# switch.net
KiCad netlist of a schematic drawn in Altium Designer
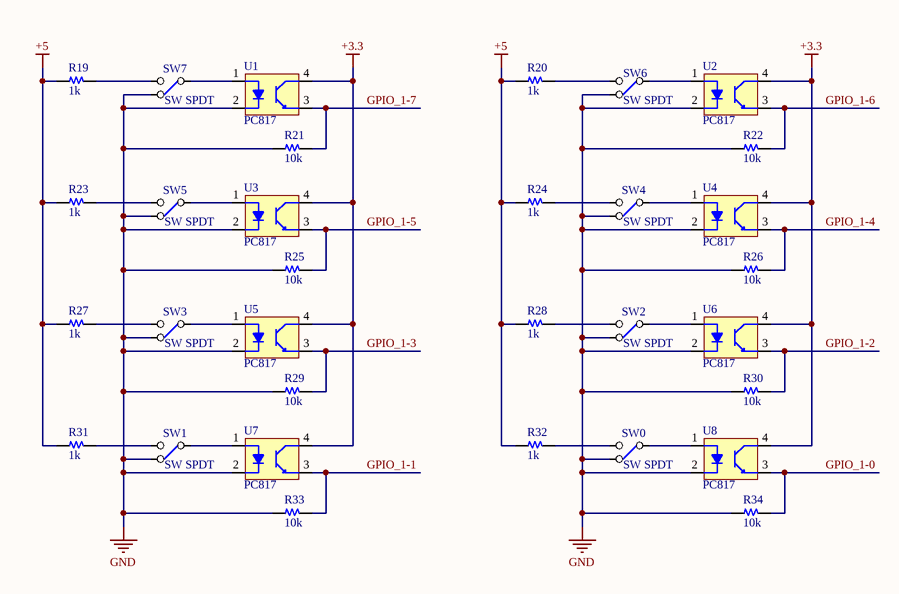
[diagram p0: switch.SchDoc]

(export (version "E")
  (design (tool "Eeschema 10.0.6"))
  (components
    (comp (ref "R19")
      (value "1k")
      (footprint "R 0603")
      (description "Resistor")
      (libsource (lib "chipfc_libs") (part "Resistor"))
    )
    (comp (ref "R20")
      (value "1k")
      (footprint "R 0603")
      (description "Resistor")
      (libsource (lib "chipfc_libs") (part "Resistor"))
    )
    (comp (ref "R21")
      (value "10k")
      (footprint "R 0603")
      (description "Resistor")
      (libsource (lib "chipfc_libs") (part "Resistor"))
    )
    (comp (ref "R22")
      (value "10k")
      (footprint "R 0603")
      (description "Resistor")
      (libsource (lib "chipfc_libs") (part "Resistor"))
    )
    (comp (ref "R23")
      (value "1k")
      (footprint "R 0603")
      (description "Resistor")
      (libsource (lib "chipfc_libs") (part "Resistor"))
    )
    (comp (ref "R24")
      (value "1k")
      (footprint "R 0603")
      (description "Resistor")
      (libsource (lib "chipfc_libs") (part "Resistor"))
    )
    (comp (ref "R25")
      (value "10k")
      (footprint "R 0603")
      (description "Resistor")
      (libsource (lib "chipfc_libs") (part "Resistor"))
    )
    (comp (ref "R26")
      (value "10k")
      (footprint "R 0603")
      (description "Resistor")
      (libsource (lib "chipfc_libs") (part "Resistor"))
    )
    (comp (ref "R27")
      (value "1k")
      (footprint "R 0603")
      (description "Resistor")
      (libsource (lib "chipfc_libs") (part "Resistor"))
    )
    (comp (ref "R28")
      (value "1k")
      (footprint "R 0603")
      (description "Resistor")
      (libsource (lib "chipfc_libs") (part "Resistor"))
    )
    (comp (ref "R29")
      (value "10k")
      (footprint "R 0603")
      (description "Resistor")
      (libsource (lib "chipfc_libs") (part "Resistor"))
    )
    (comp (ref "R30")
      (value "10k")
      (footprint "R 0603")
      (description "Resistor")
      (libsource (lib "chipfc_libs") (part "Resistor"))
    )
    (comp (ref "R31")
      (value "1k")
      (footprint "R 0603")
      (description "Resistor")
      (libsource (lib "chipfc_libs") (part "Resistor"))
    )
    (comp (ref "R32")
      (value "1k")
      (footprint "R 0603")
      (description "Resistor")
      (libsource (lib "chipfc_libs") (part "Resistor"))
    )
    (comp (ref "R33")
      (value "10k")
      (footprint "R 0603")
      (description "Resistor")
      (libsource (lib "chipfc_libs") (part "Resistor"))
    )
    (comp (ref "R34")
      (value "10k")
      (footprint "R 0603")
      (description "Resistor")
      (libsource (lib "chipfc_libs") (part "Resistor"))
    )
    (comp (ref "SW0")
      (value "SW SPDT")
      (footprint "SW/3/SPDT/SS12D10")
      (libsource (lib "chipfc_libs") (part "SW SPDT"))
    )
    (comp (ref "SW1")
      (value "SW SPDT")
      (footprint "SW/3/SPDT/SS12D10")
      (libsource (lib "chipfc_libs") (part "SW SPDT"))
    )
    (comp (ref "SW2")
      (value "SW SPDT")
      (footprint "SW/3/SPDT/SS12D10")
      (libsource (lib "chipfc_libs") (part "SW SPDT"))
    )
    (comp (ref "SW3")
      (value "SW SPDT")
      (footprint "SW/3/SPDT/SS12D10")
      (libsource (lib "chipfc_libs") (part "SW SPDT"))
    )
    (comp (ref "SW4")
      (value "SW SPDT")
      (footprint "SW/3/SPDT/SS12D10")
      (libsource (lib "chipfc_libs") (part "SW SPDT"))
    )
    (comp (ref "SW5")
      (value "SW SPDT")
      (footprint "SW/3/SPDT/SS12D10")
      (libsource (lib "chipfc_libs") (part "SW SPDT"))
    )
    (comp (ref "SW6")
      (value "SW SPDT")
      (footprint "SW/3/SPDT/SS12D10")
      (libsource (lib "chipfc_libs") (part "SW SPDT"))
    )
    (comp (ref "SW7")
      (value "SW SPDT")
      (footprint "SW/3/SPDT/SS12D10")
      (libsource (lib "chipfc_libs") (part "SW SPDT"))
    )
    (comp (ref "U1")
      (value "PC817")
      (footprint "SOP4 - PC817")
      (description "Opto PC817B")
      (libsource (lib "bs_libs") (part "PC817"))
    )
    (comp (ref "U2")
      (value "PC817")
      (footprint "SOP4 - PC817")
      (description "Opto PC817B")
      (libsource (lib "bs_libs") (part "PC817"))
    )
    (comp (ref "U3")
      (value "PC817")
      (footprint "SOP4 - PC817")
      (description "Opto PC817B")
      (libsource (lib "bs_libs") (part "PC817"))
    )
    (comp (ref "U4")
      (value "PC817")
      (footprint "SOP4 - PC817")
      (description "Opto PC817B")
      (libsource (lib "bs_libs") (part "PC817"))
    )
    (comp (ref "U5")
      (value "PC817")
      (footprint "SOP4 - PC817")
      (description "Opto PC817B")
      (libsource (lib "bs_libs") (part "PC817"))
    )
    (comp (ref "U6")
      (value "PC817")
      (footprint "SOP4 - PC817")
      (description "Opto PC817B")
      (libsource (lib "bs_libs") (part "PC817"))
    )
    (comp (ref "U7")
      (value "PC817")
      (footprint "SOP4 - PC817")
      (description "Opto PC817B")
      (libsource (lib "bs_libs") (part "PC817"))
    )
    (comp (ref "U8")
      (value "PC817")
      (footprint "SOP4 - PC817")
      (description "Opto PC817B")
      (libsource (lib "bs_libs") (part "PC817"))
    )
  )
  (nets
    (net (code "1") (name "+3.3") (class "Default")
      (node (ref "U1") (pin "4") (pinfunction "C_4") (pintype "passive"))
      (node (ref "U2") (pin "4") (pinfunction "C_4") (pintype "passive"))
      (node (ref "U3") (pin "4") (pinfunction "C_4") (pintype "passive"))
      (node (ref "U4") (pin "4") (pinfunction "C_4") (pintype "passive"))
      (node (ref "U5") (pin "4") (pinfunction "C_4") (pintype "passive"))
      (node (ref "U6") (pin "4") (pinfunction "C_4") (pintype "passive"))
      (node (ref "U7") (pin "4") (pinfunction "C_4") (pintype "passive"))
      (node (ref "U8") (pin "4") (pinfunction "C_4") (pintype "passive"))
    )
    (net (code "2") (name "+5") (class "Default")
      (node (ref "R19") (pin "1") (pinfunction "1_1") (pintype "passive"))
      (node (ref "R20") (pin "1") (pinfunction "1_1") (pintype "passive"))
      (node (ref "R23") (pin "1") (pinfunction "1_1") (pintype "passive"))
      (node (ref "R24") (pin "1") (pinfunction "1_1") (pintype "passive"))
      (node (ref "R27") (pin "1") (pinfunction "1_1") (pintype "passive"))
      (node (ref "R28") (pin "1") (pinfunction "1_1") (pintype "passive"))
      (node (ref "R31") (pin "1") (pinfunction "1_1") (pintype "passive"))
      (node (ref "R32") (pin "1") (pinfunction "1_1") (pintype "passive"))
    )
    (net (code "3") (name "/GPIO_1-0") (class "Default")
      (node (ref "R34") (pin "2") (pinfunction "2_2") (pintype "passive"))
      (node (ref "U8") (pin "3") (pinfunction "E_3") (pintype "passive"))
    )
    (net (code "4") (name "/GPIO_1-1") (class "Default")
      (node (ref "R33") (pin "2") (pinfunction "2_2") (pintype "passive"))
      (node (ref "U7") (pin "3") (pinfunction "E_3") (pintype "passive"))
    )
    (net (code "5") (name "/GPIO_1-2") (class "Default")
      (node (ref "R30") (pin "2") (pinfunction "2_2") (pintype "passive"))
      (node (ref "U6") (pin "3") (pinfunction "E_3") (pintype "passive"))
    )
    (net (code "6") (name "/GPIO_1-3") (class "Default")
      (node (ref "R29") (pin "2") (pinfunction "2_2") (pintype "passive"))
      (node (ref "U5") (pin "3") (pinfunction "E_3") (pintype "passive"))
    )
    (net (code "7") (name "/GPIO_1-4") (class "Default")
      (node (ref "R26") (pin "2") (pinfunction "2_2") (pintype "passive"))
      (node (ref "U4") (pin "3") (pinfunction "E_3") (pintype "passive"))
    )
    (net (code "8") (name "/GPIO_1-5") (class "Default")
      (node (ref "R25") (pin "2") (pinfunction "2_2") (pintype "passive"))
      (node (ref "U3") (pin "3") (pinfunction "E_3") (pintype "passive"))
    )
    (net (code "9") (name "/GPIO_1-6") (class "Default")
      (node (ref "R22") (pin "2") (pinfunction "2_2") (pintype "passive"))
      (node (ref "U2") (pin "3") (pinfunction "E_3") (pintype "passive"))
    )
    (net (code "10") (name "/GPIO_1-7") (class "Default")
      (node (ref "R21") (pin "2") (pinfunction "2_2") (pintype "passive"))
      (node (ref "U1") (pin "3") (pinfunction "E_3") (pintype "passive"))
    )
    (net (code "11") (name "GND") (class "Default")
      (node (ref "R21") (pin "1") (pinfunction "1_1") (pintype "passive"))
      (node (ref "R22") (pin "1") (pinfunction "1_1") (pintype "passive"))
      (node (ref "R25") (pin "1") (pinfunction "1_1") (pintype "passive"))
      (node (ref "R26") (pin "1") (pinfunction "1_1") (pintype "passive"))
      (node (ref "R29") (pin "1") (pinfunction "1_1") (pintype "passive"))
      (node (ref "R30") (pin "1") (pinfunction "1_1") (pintype "passive"))
      (node (ref "R33") (pin "1") (pinfunction "1_1") (pintype "passive"))
      (node (ref "R34") (pin "1") (pinfunction "1_1") (pintype "passive"))
      (node (ref "SW0") (pin "1") (pinfunction "NC1_1") (pintype "passive"))
      (node (ref "SW1") (pin "1") (pinfunction "NC1_1") (pintype "passive"))
      (node (ref "SW2") (pin "1") (pinfunction "NC1_1") (pintype "passive"))
      (node (ref "SW3") (pin "1") (pinfunction "NC1_1") (pintype "passive"))
      (node (ref "SW4") (pin "1") (pinfunction "NC1_1") (pintype "passive"))
      (node (ref "SW5") (pin "1") (pinfunction "NC1_1") (pintype "passive"))
      (node (ref "SW6") (pin "1") (pinfunction "NC1_1") (pintype "passive"))
      (node (ref "SW7") (pin "1") (pinfunction "NC1_1") (pintype "passive"))
      (node (ref "U1") (pin "2") (pinfunction "K_2") (pintype "passive"))
      (node (ref "U2") (pin "2") (pinfunction "K_2") (pintype "passive"))
      (node (ref "U3") (pin "2") (pinfunction "K_2") (pintype "passive"))
      (node (ref "U4") (pin "2") (pinfunction "K_2") (pintype "passive"))
      (node (ref "U5") (pin "2") (pinfunction "K_2") (pintype "passive"))
      (node (ref "U6") (pin "2") (pinfunction "K_2") (pintype "passive"))
      (node (ref "U7") (pin "2") (pinfunction "K_2") (pintype "passive"))
      (node (ref "U8") (pin "2") (pinfunction "K_2") (pintype "passive"))
    )
    (net (code "12") (name "Net-(SW0-COMMON1)") (class "Default")
      (node (ref "SW0") (pin "2") (pinfunction "COMMON1_2") (pintype "passive"))
      (node (ref "U8") (pin "1") (pinfunction "A_1") (pintype "passive"))
    )
    (net (code "13") (name "Net-(SW0-NO1)") (class "Default")
      (node (ref "R32") (pin "2") (pinfunction "2_2") (pintype "passive"))
      (node (ref "SW0") (pin "3") (pinfunction "NO1_3") (pintype "passive"))
    )
    (net (code "14") (name "Net-(SW1-COMMON1)") (class "Default")
      (node (ref "SW1") (pin "2") (pinfunction "COMMON1_2") (pintype "passive"))
      (node (ref "U7") (pin "1") (pinfunction "A_1") (pintype "passive"))
    )
    (net (code "15") (name "Net-(SW1-NO1)") (class "Default")
      (node (ref "R31") (pin "2") (pinfunction "2_2") (pintype "passive"))
      (node (ref "SW1") (pin "3") (pinfunction "NO1_3") (pintype "passive"))
    )
    (net (code "16") (name "Net-(SW2-COMMON1)") (class "Default")
      (node (ref "SW2") (pin "2") (pinfunction "COMMON1_2") (pintype "passive"))
      (node (ref "U6") (pin "1") (pinfunction "A_1") (pintype "passive"))
    )
    (net (code "17") (name "Net-(SW2-NO1)") (class "Default")
      (node (ref "R28") (pin "2") (pinfunction "2_2") (pintype "passive"))
      (node (ref "SW2") (pin "3") (pinfunction "NO1_3") (pintype "passive"))
    )
    (net (code "18") (name "Net-(SW3-COMMON1)") (class "Default")
      (node (ref "SW3") (pin "2") (pinfunction "COMMON1_2") (pintype "passive"))
      (node (ref "U5") (pin "1") (pinfunction "A_1") (pintype "passive"))
    )
    (net (code "19") (name "Net-(SW3-NO1)") (class "Default")
      (node (ref "R27") (pin "2") (pinfunction "2_2") (pintype "passive"))
      (node (ref "SW3") (pin "3") (pinfunction "NO1_3") (pintype "passive"))
    )
    (net (code "20") (name "Net-(SW4-COMMON1)") (class "Default")
      (node (ref "SW4") (pin "2") (pinfunction "COMMON1_2") (pintype "passive"))
      (node (ref "U4") (pin "1") (pinfunction "A_1") (pintype "passive"))
    )
    (net (code "21") (name "Net-(SW4-NO1)") (class "Default")
      (node (ref "R24") (pin "2") (pinfunction "2_2") (pintype "passive"))
      (node (ref "SW4") (pin "3") (pinfunction "NO1_3") (pintype "passive"))
    )
    (net (code "22") (name "Net-(SW5-COMMON1)") (class "Default")
      (node (ref "SW5") (pin "2") (pinfunction "COMMON1_2") (pintype "passive"))
      (node (ref "U3") (pin "1") (pinfunction "A_1") (pintype "passive"))
    )
    (net (code "23") (name "Net-(SW5-NO1)") (class "Default")
      (node (ref "R23") (pin "2") (pinfunction "2_2") (pintype "passive"))
      (node (ref "SW5") (pin "3") (pinfunction "NO1_3") (pintype "passive"))
    )
    (net (code "24") (name "Net-(SW6-COMMON1)") (class "Default")
      (node (ref "SW6") (pin "2") (pinfunction "COMMON1_2") (pintype "passive"))
      (node (ref "U2") (pin "1") (pinfunction "A_1") (pintype "passive"))
    )
    (net (code "25") (name "Net-(SW6-NO1)") (class "Default")
      (node (ref "R20") (pin "2") (pinfunction "2_2") (pintype "passive"))
      (node (ref "SW6") (pin "3") (pinfunction "NO1_3") (pintype "passive"))
    )
    (net (code "26") (name "Net-(SW7-COMMON1)") (class "Default")
      (node (ref "SW7") (pin "2") (pinfunction "COMMON1_2") (pintype "passive"))
      (node (ref "U1") (pin "1") (pinfunction "A_1") (pintype "passive"))
    )
    (net (code "27") (name "Net-(SW7-NO1)") (class "Default")
      (node (ref "R19") (pin "2") (pinfunction "2_2") (pintype "passive"))
      (node (ref "SW7") (pin "3") (pinfunction "NO1_3") (pintype "passive"))
    )
  )
)
